# carry-select.net
KiCad netlist of a schematic drawn in EAGLE
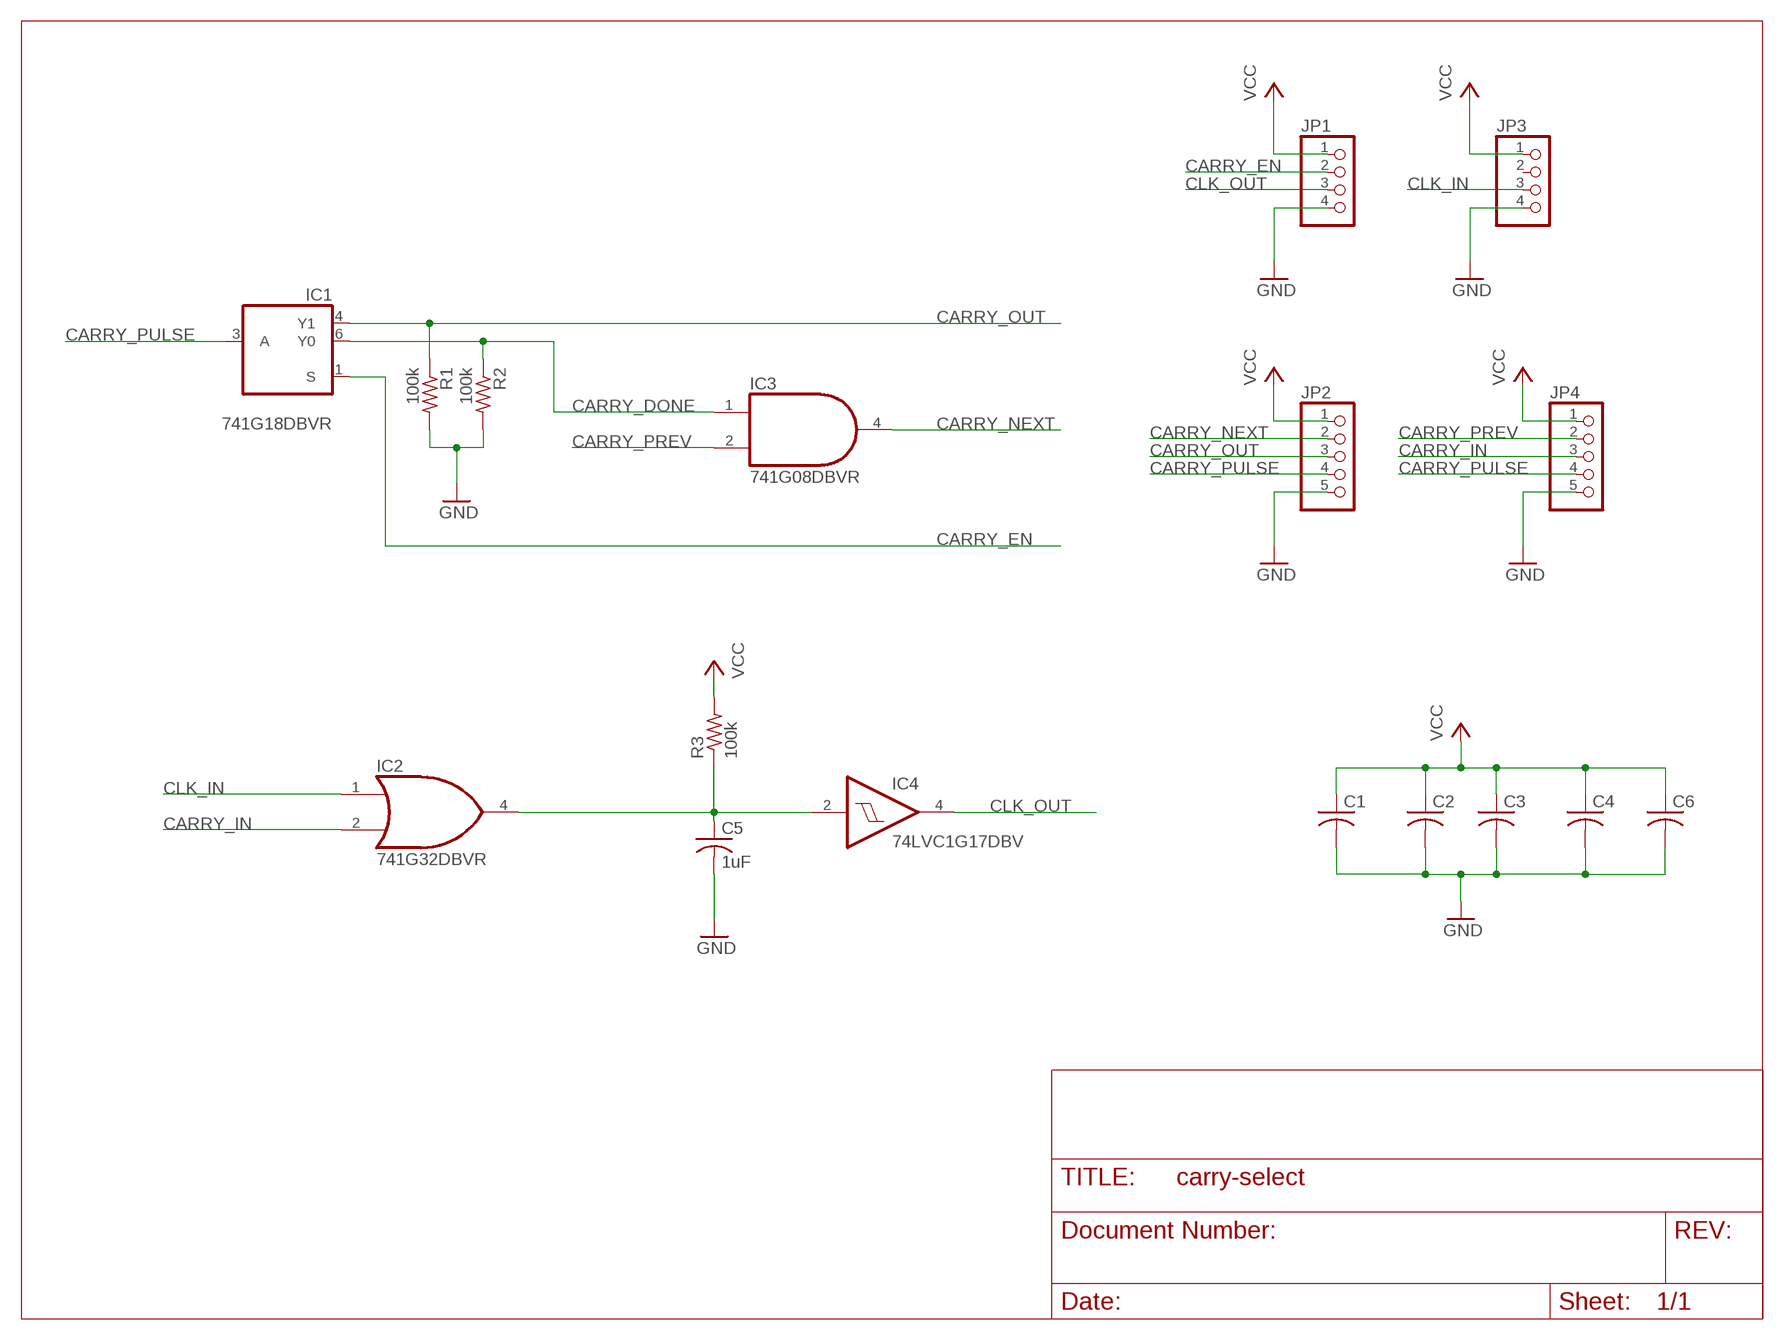
[diagram p0: schematic, sheet 1]

(export (version "E")
  (design (tool "Eeschema 10.0.6"))
  (components
    (comp (ref "C1")
      (value "C-USC0603K")
      (footprint "eagle-import:C0603K")
      (libsource (lib "eagle-import") (part "C-USC0603K"))
    )
    (comp (ref "C2")
      (value "C-USC0603K")
      (footprint "eagle-import:C0603K")
      (libsource (lib "eagle-import") (part "C-USC0603K"))
    )
    (comp (ref "C3")
      (value "C-USC0603K")
      (footprint "eagle-import:C0603K")
      (libsource (lib "eagle-import") (part "C-USC0603K"))
    )
    (comp (ref "C4")
      (value "C-USC0603K")
      (footprint "eagle-import:C0603K")
      (libsource (lib "eagle-import") (part "C-USC0603K"))
    )
    (comp (ref "C5")
      (value "1uF")
      (footprint "eagle-import:C0603K")
      (libsource (lib "eagle-import") (part "C-USC0603K"))
    )
    (comp (ref "C6")
      (value "C-USC0603K")
      (footprint "eagle-import:C0603K")
      (libsource (lib "eagle-import") (part "C-USC0603K"))
    )
    (comp (ref "IC1")
      (value "741G18DBVR")
      (footprint "eagle-import:DBV_R-PDSO-G6")
      (libsource (lib "eagle-import") (part "741G18"))
    )
    (comp (ref "IC2")
      (value "741G32DBVR")
      (footprint "eagle-import:SOT23-5")
      (libsource (lib "eagle-import") (part "741G32DBVAHC"))
    )
    (comp (ref "IC3")
      (value "741G08DBVR")
      (footprint "eagle-import:SOT23-5")
      (libsource (lib "eagle-import") (part "741G08DBVLVC"))
    )
    (comp (ref "IC4")
      (value "74LVC1G17DBV")
      (footprint "eagle-import:SOT23-5")
      (libsource (lib "eagle-import") (part "741G17DBVLVC"))
    )
    (comp (ref "JP1")
      (value "PINHD-1X4")
      (footprint "eagle-import:1X04")
      (libsource (lib "eagle-import") (part "PINHD-1X4"))
    )
    (comp (ref "JP2")
      (value "PINHD-1X5")
      (footprint "eagle-import:1X05")
      (libsource (lib "eagle-import") (part "PINHD-1X5"))
    )
    (comp (ref "JP3")
      (value "PINHD-1X4")
      (footprint "eagle-import:1X04")
      (libsource (lib "eagle-import") (part "PINHD-1X4"))
    )
    (comp (ref "JP4")
      (value "PINHD-1X5")
      (footprint "eagle-import:1X05")
      (libsource (lib "eagle-import") (part "PINHD-1X5"))
    )
    (comp (ref "R1")
      (value "100k")
      (footprint "eagle-import:R0603")
      (libsource (lib "eagle-import") (part "R-US_R0603"))
    )
    (comp (ref "R2")
      (value "100k")
      (footprint "eagle-import:R0603")
      (libsource (lib "eagle-import") (part "R-US_R0603"))
    )
    (comp (ref "R3")
      (value "100k")
      (footprint "eagle-import:R0603")
      (libsource (lib "eagle-import") (part "R-US_R0603"))
    )
  )
  (nets
    (net (code "1") (name "/CARRY_DONE") (class "Default")
      (node (ref "IC1") (pin "6") (pinfunction "Y0_6") (pintype "bidirectional"))
      (node (ref "IC3") (pin "1") (pinfunction "I0_1") (pintype "input"))
      (node (ref "R2") (pin "1") (pinfunction "1_1") (pintype "passive"))
    )
    (net (code "2") (name "/CARRY_EN") (class "Default")
      (node (ref "IC1") (pin "1") (pinfunction "S_1") (pintype "input"))
      (node (ref "JP1") (pin "2") (pinfunction "2_2") (pintype "passive"))
    )
    (net (code "3") (name "/CARRY_IN") (class "Default")
      (node (ref "IC2") (pin "2") (pinfunction "I1_2") (pintype "input"))
      (node (ref "JP4") (pin "3") (pinfunction "3_3") (pintype "passive"))
    )
    (net (code "4") (name "/CARRY_NEXT") (class "Default")
      (node (ref "IC3") (pin "4") (pinfunction "O_4") (pintype "output"))
      (node (ref "JP2") (pin "2") (pinfunction "2_2") (pintype "passive"))
    )
    (net (code "5") (name "/CARRY_OUT") (class "Default")
      (node (ref "IC1") (pin "4") (pinfunction "Y1_4") (pintype "bidirectional"))
      (node (ref "JP2") (pin "3") (pinfunction "3_3") (pintype "passive"))
      (node (ref "R1") (pin "1") (pinfunction "1_1") (pintype "passive"))
    )
    (net (code "6") (name "/CARRY_PREV") (class "Default")
      (node (ref "IC3") (pin "2") (pinfunction "I1_2") (pintype "input"))
      (node (ref "JP4") (pin "2") (pinfunction "2_2") (pintype "passive"))
    )
    (net (code "7") (name "/CARRY_PULSE") (class "Default")
      (node (ref "IC1") (pin "3") (pinfunction "A_3") (pintype "bidirectional"))
      (node (ref "JP2") (pin "4") (pinfunction "4_4") (pintype "passive"))
      (node (ref "JP4") (pin "4") (pinfunction "4_4") (pintype "passive"))
    )
    (net (code "8") (name "/CLK_IN") (class "Default")
      (node (ref "IC2") (pin "1") (pinfunction "I0_1") (pintype "input"))
      (node (ref "JP3") (pin "3") (pinfunction "3_3") (pintype "passive"))
    )
    (net (code "9") (name "/CLK_OUT") (class "Default")
      (node (ref "IC4") (pin "4") (pinfunction "O_4") (pintype "output"))
      (node (ref "JP1") (pin "3") (pinfunction "3_3") (pintype "passive"))
    )
    (net (code "10") (name "GND") (class "Default")
      (node (ref "C1") (pin "2") (pinfunction "2_2") (pintype "passive"))
      (node (ref "C2") (pin "2") (pinfunction "2_2") (pintype "passive"))
      (node (ref "C3") (pin "2") (pinfunction "2_2") (pintype "passive"))
      (node (ref "C4") (pin "2") (pinfunction "2_2") (pintype "passive"))
      (node (ref "C5") (pin "2") (pinfunction "2_2") (pintype "passive"))
      (node (ref "C6") (pin "2") (pinfunction "2_2") (pintype "passive"))
      (node (ref "JP1") (pin "4") (pinfunction "4_4") (pintype "passive"))
      (node (ref "JP2") (pin "5") (pinfunction "5_5") (pintype "passive"))
      (node (ref "JP3") (pin "4") (pinfunction "4_4") (pintype "passive"))
      (node (ref "JP4") (pin "5") (pinfunction "5_5") (pintype "passive"))
      (node (ref "R1") (pin "2") (pinfunction "2_2") (pintype "passive"))
      (node (ref "R2") (pin "2") (pinfunction "2_2") (pintype "passive"))
    )
    (net (code "11") (name "Net-(IC2A-O)") (class "Default")
      (node (ref "C5") (pin "1") (pinfunction "1_1") (pintype "passive"))
      (node (ref "IC2") (pin "4") (pinfunction "O_4") (pintype "output"))
      (node (ref "IC4") (pin "2") (pinfunction "I_2") (pintype "input"))
      (node (ref "R3") (pin "1") (pinfunction "1_1") (pintype "passive"))
    )
    (net (code "12") (name "VCC") (class "Default")
      (node (ref "C1") (pin "1") (pinfunction "1_1") (pintype "passive"))
      (node (ref "C2") (pin "1") (pinfunction "1_1") (pintype "passive"))
      (node (ref "C3") (pin "1") (pinfunction "1_1") (pintype "passive"))
      (node (ref "C4") (pin "1") (pinfunction "1_1") (pintype "passive"))
      (node (ref "C6") (pin "1") (pinfunction "1_1") (pintype "passive"))
      (node (ref "JP1") (pin "1") (pinfunction "1_1") (pintype "passive"))
      (node (ref "JP2") (pin "1") (pinfunction "1_1") (pintype "passive"))
      (node (ref "JP3") (pin "1") (pinfunction "1_1") (pintype "passive"))
      (node (ref "JP4") (pin "1") (pinfunction "1_1") (pintype "passive"))
      (node (ref "R3") (pin "2") (pinfunction "2_2") (pintype "passive"))
    )
    (net (code "13") (name "unconnected-(JP3-Pad2)") (class "Default")
      (node (ref "JP3") (pin "2") (pinfunction "2_2") (pintype "passive"))
    )
  )
)
